# ionode.net
KiCad netlist of a schematic drawn in EAGLE
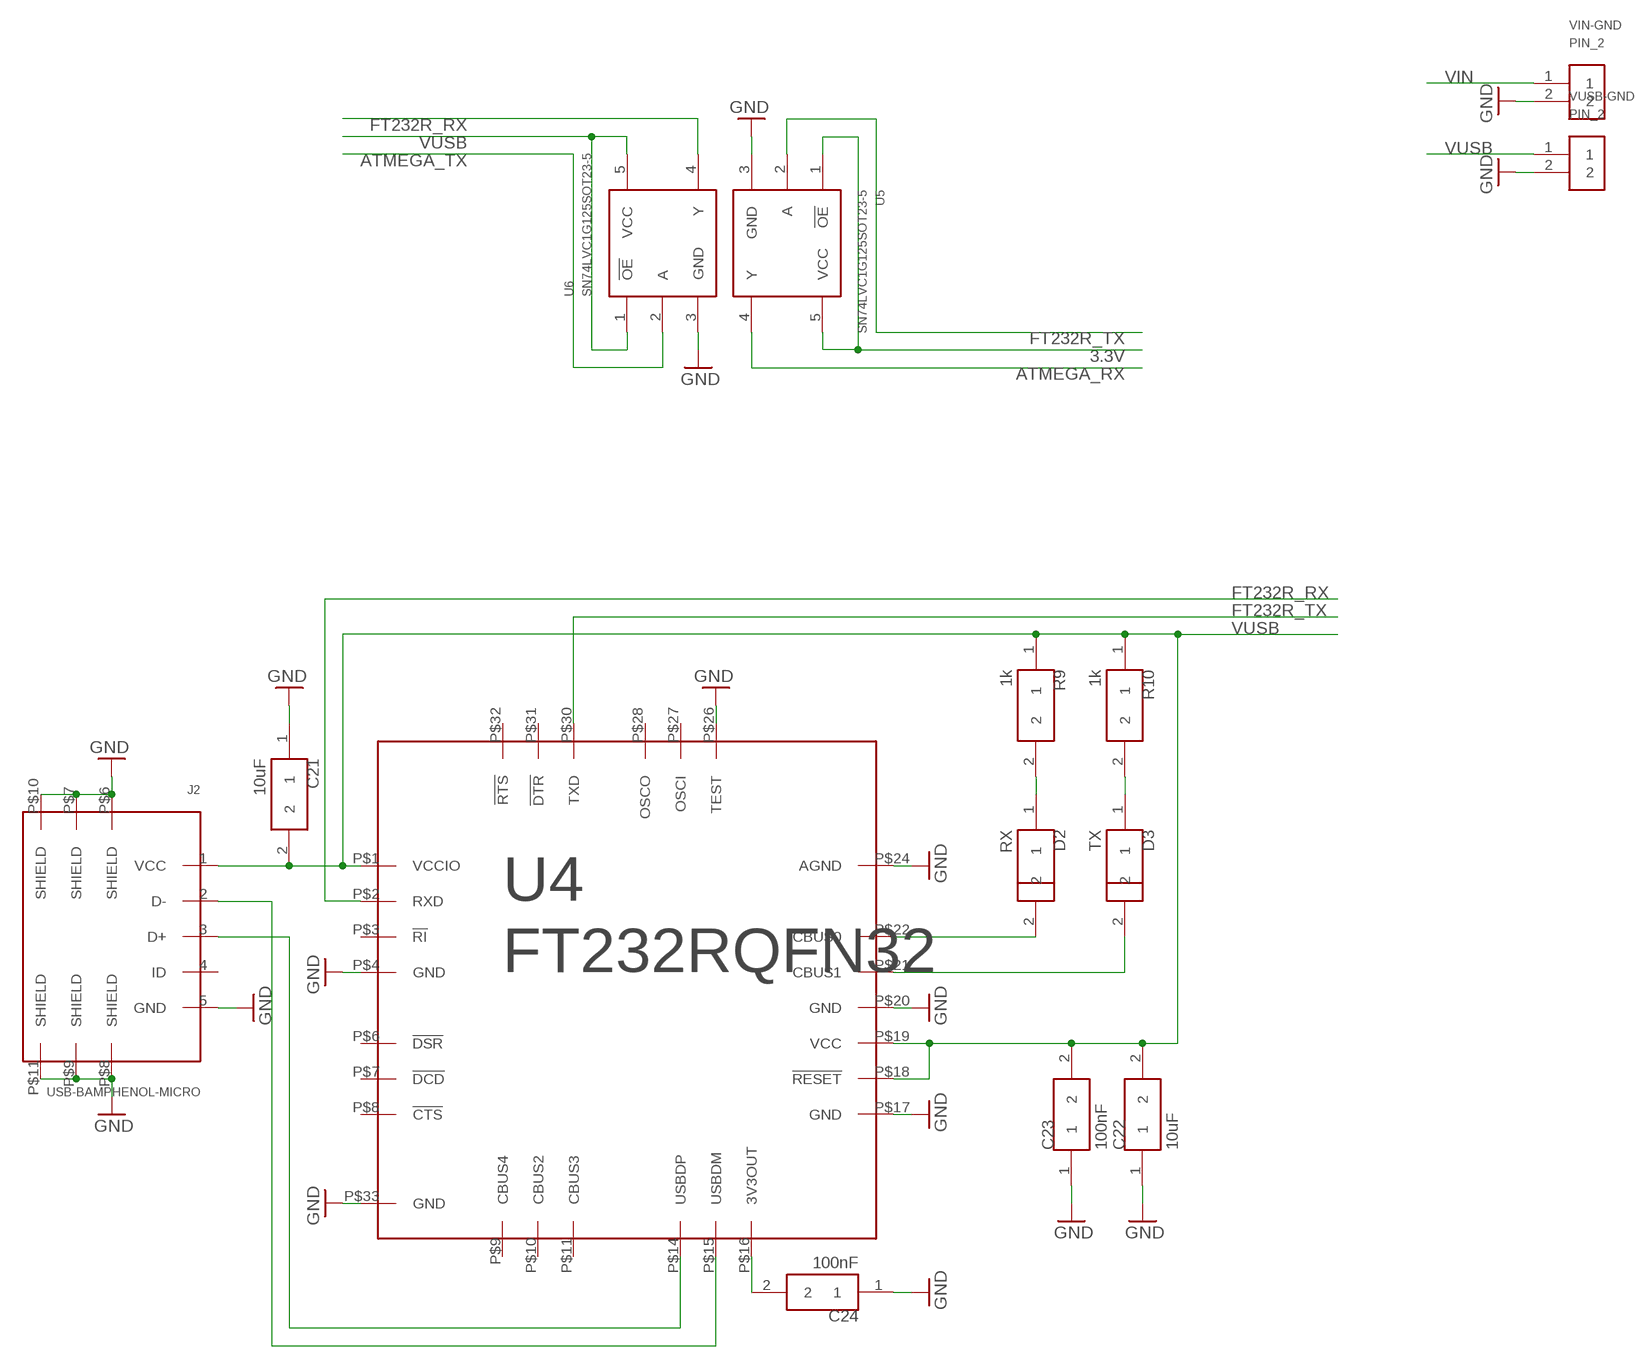
[diagram p0: schematic, sheet 1, part 1 of 2]
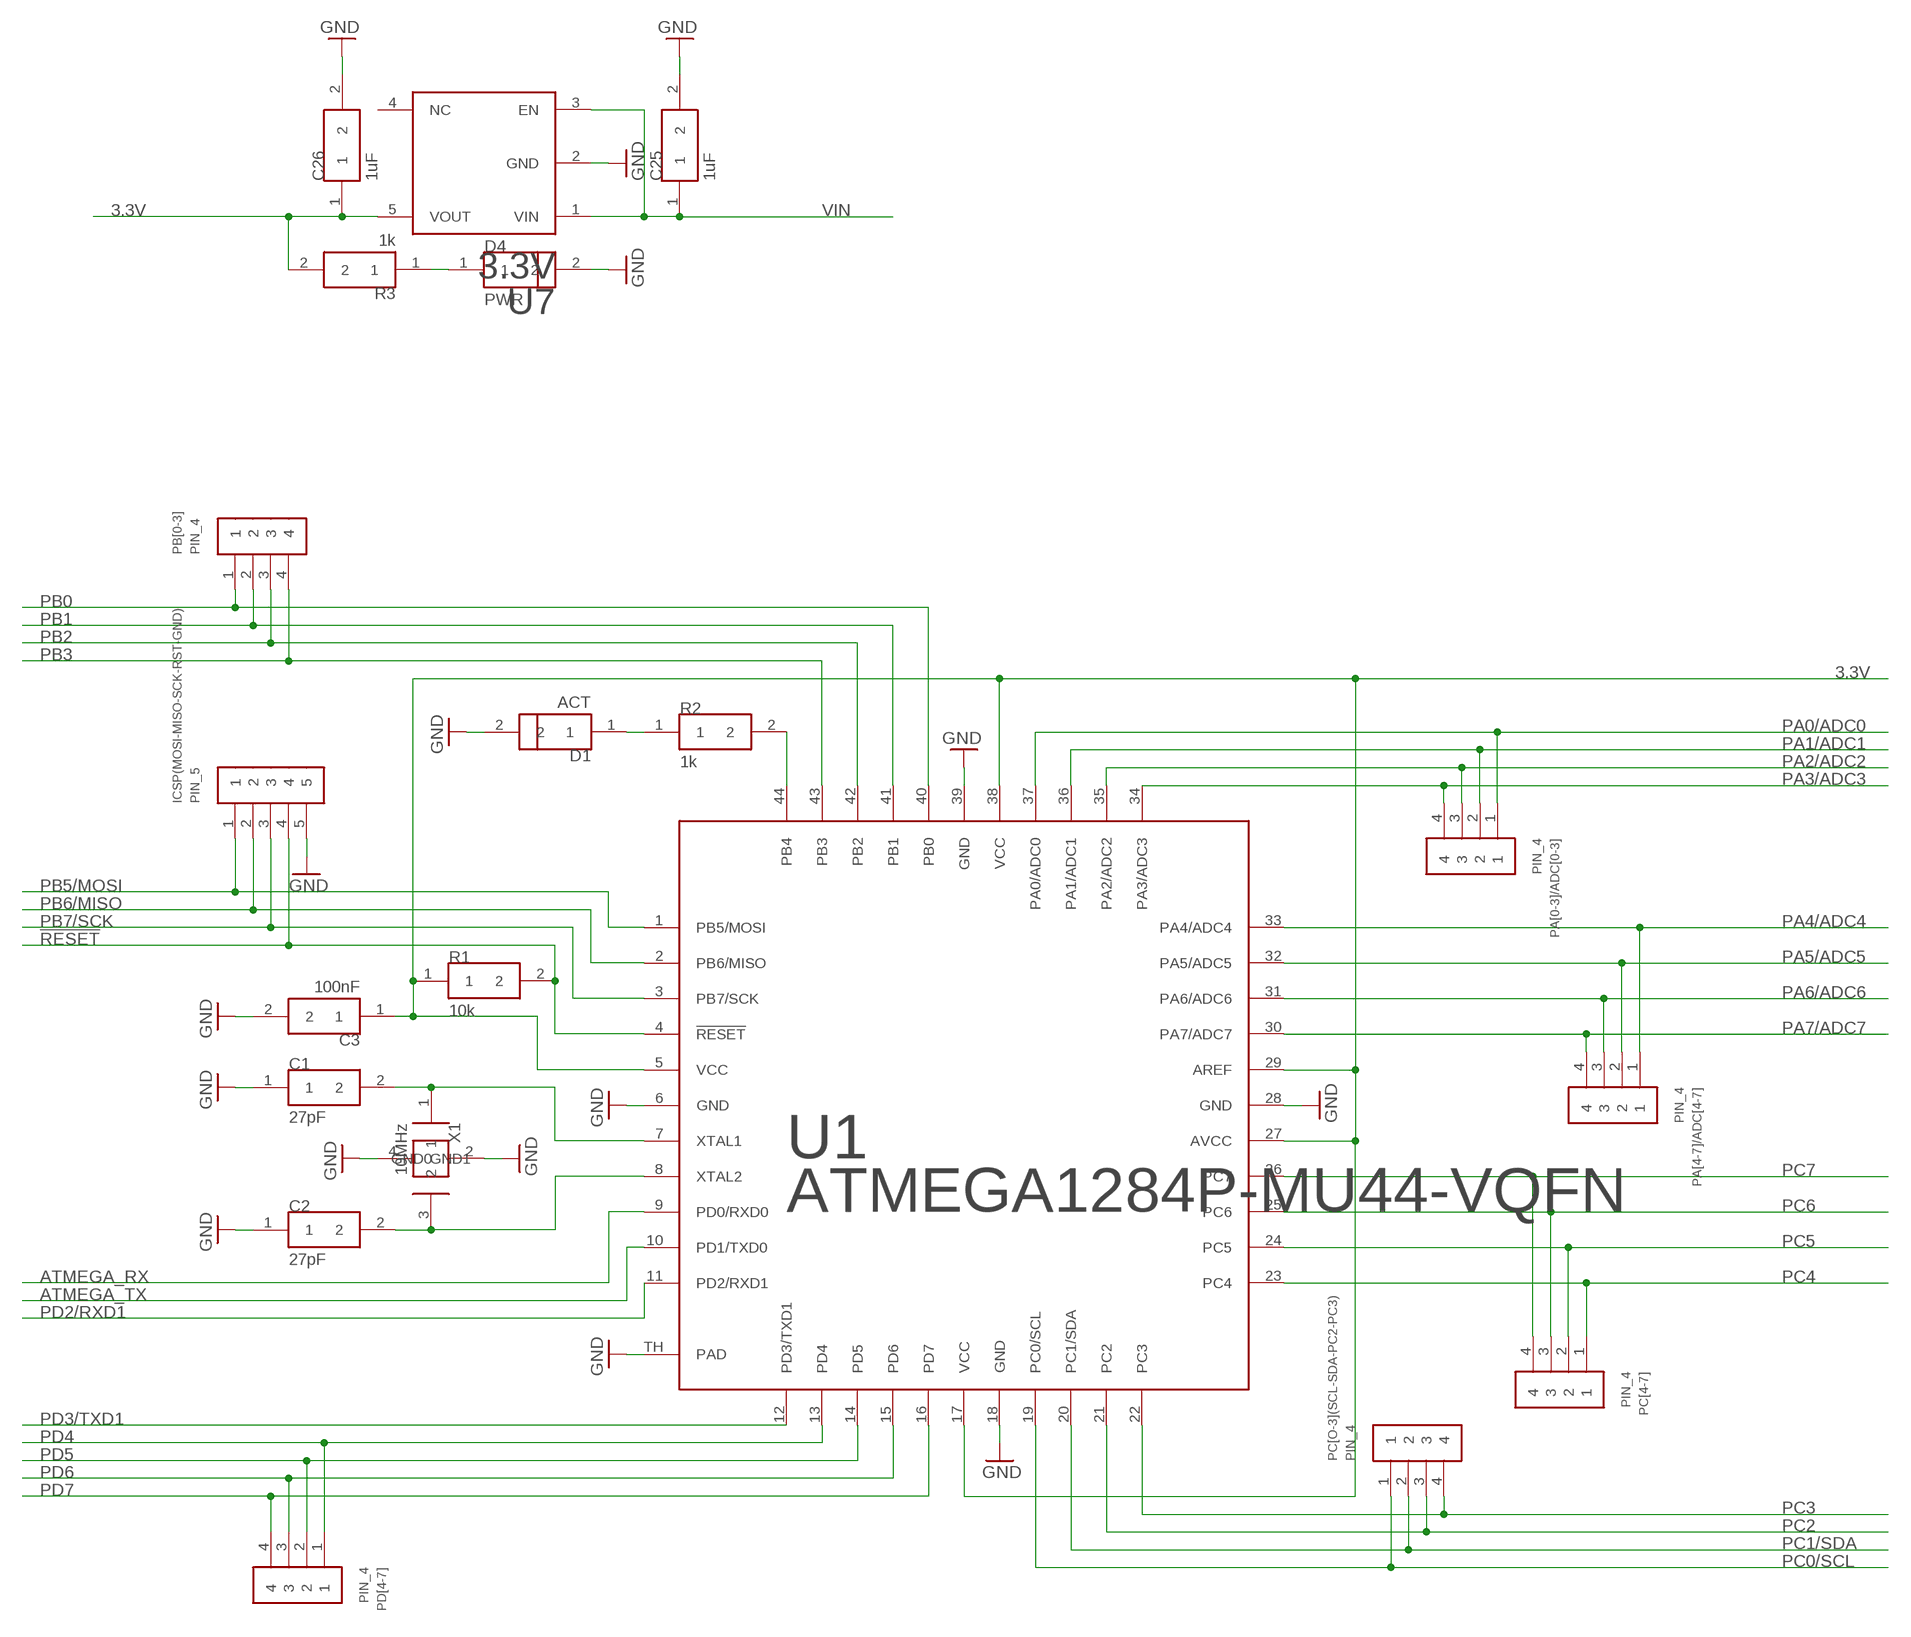
[diagram p1: schematic, sheet 1, part 2 of 2]

(export (version "E")
  (design (tool "Eeschema 10.0.6"))
  (components
    (comp (ref "C1")
      (value "27pF")
      (footprint "eagle-import:0805")
      (libsource (lib "eagle-import") (part "CAP0805"))
    )
    (comp (ref "C2")
      (value "27pF")
      (footprint "eagle-import:0805")
      (libsource (lib "eagle-import") (part "CAP0805"))
    )
    (comp (ref "C3")
      (value "100nF")
      (footprint "eagle-import:0805")
      (libsource (lib "eagle-import") (part "CAP0805"))
    )
    (comp (ref "C21")
      (value "10uF")
      (footprint "eagle-import:0805")
      (libsource (lib "eagle-import") (part "CAP0805"))
    )
    (comp (ref "C22")
      (value "10uF")
      (footprint "eagle-import:0805")
      (libsource (lib "eagle-import") (part "CAP0805"))
    )
    (comp (ref "C23")
      (value "100nF")
      (footprint "eagle-import:0805")
      (libsource (lib "eagle-import") (part "CAP0805"))
    )
    (comp (ref "C24")
      (value "100nF")
      (footprint "eagle-import:0805")
      (libsource (lib "eagle-import") (part "CAP0805"))
    )
    (comp (ref "C25")
      (value "1uF")
      (footprint "eagle-import:0805")
      (libsource (lib "eagle-import") (part "CAP0805"))
    )
    (comp (ref "C26")
      (value "1uF")
      (footprint "eagle-import:0805")
      (libsource (lib "eagle-import") (part "CAP0805"))
    )
    (comp (ref "D1")
      (value "ACT")
      (footprint "eagle-import:0805")
      (libsource (lib "eagle-import") (part "LED0805"))
    )
    (comp (ref "D2")
      (value "RX")
      (footprint "eagle-import:0805")
      (libsource (lib "eagle-import") (part "LED0805"))
    )
    (comp (ref "D3")
      (value "TX")
      (footprint "eagle-import:0805")
      (libsource (lib "eagle-import") (part "LED0805"))
    )
    (comp (ref "D4")
      (value "PWR")
      (footprint "eagle-import:0805")
      (libsource (lib "eagle-import") (part "LED0805"))
    )
    (comp (ref "ICSP(MOSI-MISO-SCK-RST-GND)")
      (value "PIN_5")
      (footprint "eagle-import:PIN_5")
      (libsource (lib "eagle-import") (part "PIN_5"))
    )
    (comp (ref "J2")
      (value "USB-BAMPHENOL-MICRO")
      (footprint "eagle-import:AMPHENOL-USB-MICRO-B")
      (libsource (lib "eagle-import") (part "USB-BAMPHENOL-MICRO"))
    )
    (comp (ref "PA[0-3]/ADC[0-3]")
      (value "PIN_4")
      (footprint "eagle-import:PIN_4")
      (libsource (lib "eagle-import") (part "PIN_4"))
    )
    (comp (ref "PA[4-7]/ADC[4-7]")
      (value "PIN_4")
      (footprint "eagle-import:PIN_4")
      (libsource (lib "eagle-import") (part "PIN_4"))
    )
    (comp (ref "PB[0-3]")
      (value "PIN_4")
      (footprint "eagle-import:PIN_4")
      (libsource (lib "eagle-import") (part "PIN_4"))
    )
    (comp (ref "PC[4-7]")
      (value "PIN_4")
      (footprint "eagle-import:PIN_4")
      (libsource (lib "eagle-import") (part "PIN_4"))
    )
    (comp (ref "PC[O-3](SCL-SDA-PC2-PC3)")
      (value "PIN_4")
      (footprint "eagle-import:PIN_4")
      (libsource (lib "eagle-import") (part "PIN_4"))
    )
    (comp (ref "PD[4-7]")
      (value "PIN_4")
      (footprint "eagle-import:PIN_4")
      (libsource (lib "eagle-import") (part "PIN_4"))
    )
    (comp (ref "R1")
      (value "10k")
      (footprint "eagle-import:0805")
      (libsource (lib "eagle-import") (part "RES0805"))
    )
    (comp (ref "R2")
      (value "1k")
      (footprint "eagle-import:0805")
      (libsource (lib "eagle-import") (part "RES0805"))
    )
    (comp (ref "R3")
      (value "1k")
      (footprint "eagle-import:0805")
      (libsource (lib "eagle-import") (part "RES0805"))
    )
    (comp (ref "R9")
      (value "1k")
      (footprint "eagle-import:0805")
      (libsource (lib "eagle-import") (part "RES0805"))
    )
    (comp (ref "R10")
      (value "1k")
      (footprint "eagle-import:0805")
      (libsource (lib "eagle-import") (part "RES0805"))
    )
    (comp (ref "U1")
      (value "ATMEGA1284P-MU44-VQFN")
      (footprint "eagle-import:44-VQFN")
      (libsource (lib "eagle-import") (part "ATMEGA1284P-MU44-VQFN"))
    )
    (comp (ref "U4")
      (value "FT232RQFN32")
      (footprint "eagle-import:32-VQFN")
      (libsource (lib "eagle-import") (part "FT232RQFN32"))
    )
    (comp (ref "U5")
      (value "SN74LVC1G125SOT23-5")
      (footprint "eagle-import:SOT23-5")
      (libsource (lib "eagle-import") (part "SN74LVC1G125SOT23-5"))
    )
    (comp (ref "U6")
      (value "SN74LVC1G125SOT23-5")
      (footprint "eagle-import:SOT23-5")
      (libsource (lib "eagle-import") (part "SN74LVC1G125SOT23-5"))
    )
    (comp (ref "U7")
      (value "3.3V")
      (footprint "eagle-import:SOT23-5")
      (libsource (lib "eagle-import") (part "LP3985SOT23-5"))
    )
    (comp (ref "VIN-GND")
      (value "PIN_2")
      (footprint "eagle-import:PIN_2")
      (libsource (lib "eagle-import") (part "PIN_2"))
    )
    (comp (ref "VUSB-GND")
      (value "PIN_2")
      (footprint "eagle-import:PIN_2")
      (libsource (lib "eagle-import") (part "PIN_2"))
    )
    (comp (ref "X1")
      (value "10MHz")
      (footprint "eagle-import:XTAL_3225")
      (libsource (lib "eagle-import") (part "XTAL_GNDSMD_3225"))
    )
  )
  (nets
    (net (code "1") (name "/3.3V") (class "Default")
      (node (ref "C26") (pin "1") (pinfunction "1_1") (pintype "bidirectional"))
      (node (ref "C3") (pin "1") (pinfunction "1_1") (pintype "bidirectional"))
      (node (ref "R1") (pin "1") (pinfunction "1_1") (pintype "bidirectional"))
      (node (ref "R3") (pin "2") (pinfunction "2_2") (pintype "bidirectional"))
      (node (ref "U1") (pin "17") (pinfunction "VCC_17") (pintype "bidirectional"))
      (node (ref "U1") (pin "27") (pinfunction "AVCC_27") (pintype "bidirectional"))
      (node (ref "U1") (pin "29") (pinfunction "AREF_29") (pintype "bidirectional"))
      (node (ref "U1") (pin "38") (pinfunction "VCC_38") (pintype "bidirectional"))
      (node (ref "U1") (pin "5") (pinfunction "VCC_5") (pintype "bidirectional"))
      (node (ref "U5") (pin "1") (pinfunction "~{OE}_1") (pintype "bidirectional"))
      (node (ref "U5") (pin "5") (pinfunction "VCC_5") (pintype "bidirectional"))
      (node (ref "U7") (pin "5") (pinfunction "VOUT_5") (pintype "bidirectional"))
    )
    (net (code "2") (name "/ATMEGA_RX") (class "Default")
      (node (ref "U1") (pin "9") (pinfunction "PD0/RXD0_9") (pintype "bidirectional"))
      (node (ref "U5") (pin "4") (pinfunction "Y_4") (pintype "bidirectional"))
    )
    (net (code "3") (name "/ATMEGA_TX") (class "Default")
      (node (ref "U1") (pin "10") (pinfunction "PD1/TXD0_10") (pintype "bidirectional"))
      (node (ref "U6") (pin "2") (pinfunction "A_2") (pintype "bidirectional"))
    )
    (net (code "4") (name "/FT232R_RX") (class "Default")
      (node (ref "U4") (pin "P$2") (pinfunction "RXD_P$2") (pintype "bidirectional"))
      (node (ref "U6") (pin "4") (pinfunction "Y_4") (pintype "bidirectional"))
    )
    (net (code "5") (name "/FT232R_TX") (class "Default")
      (node (ref "U4") (pin "P$30") (pinfunction "TXD_P$30") (pintype "bidirectional"))
      (node (ref "U5") (pin "2") (pinfunction "A_2") (pintype "bidirectional"))
    )
    (net (code "6") (name "/PA0{slash}ADC0") (class "Default")
      (node (ref "PA[0-3]/ADC[0-3]") (pin "1") (pinfunction "1_1") (pintype "bidirectional"))
      (node (ref "U1") (pin "37") (pinfunction "PA0/ADC0_37") (pintype "bidirectional"))
    )
    (net (code "7") (name "/PA1{slash}ADC1") (class "Default")
      (node (ref "PA[0-3]/ADC[0-3]") (pin "2") (pinfunction "2_2") (pintype "bidirectional"))
      (node (ref "U1") (pin "36") (pinfunction "PA1/ADC1_36") (pintype "bidirectional"))
    )
    (net (code "8") (name "/PA2{slash}ADC2") (class "Default")
      (node (ref "PA[0-3]/ADC[0-3]") (pin "3") (pinfunction "3_3") (pintype "bidirectional"))
      (node (ref "U1") (pin "35") (pinfunction "PA2/ADC2_35") (pintype "bidirectional"))
    )
    (net (code "9") (name "/PA3{slash}ADC3") (class "Default")
      (node (ref "PA[0-3]/ADC[0-3]") (pin "4") (pinfunction "4_4") (pintype "bidirectional"))
      (node (ref "U1") (pin "34") (pinfunction "PA3/ADC3_34") (pintype "bidirectional"))
    )
    (net (code "10") (name "/PA4{slash}ADC4") (class "Default")
      (node (ref "PA[4-7]/ADC[4-7]") (pin "1") (pinfunction "1_1") (pintype "bidirectional"))
      (node (ref "U1") (pin "33") (pinfunction "PA4/ADC4_33") (pintype "bidirectional"))
    )
    (net (code "11") (name "/PA5{slash}ADC5") (class "Default")
      (node (ref "PA[4-7]/ADC[4-7]") (pin "2") (pinfunction "2_2") (pintype "bidirectional"))
      (node (ref "U1") (pin "32") (pinfunction "PA5/ADC5_32") (pintype "bidirectional"))
    )
    (net (code "12") (name "/PA6{slash}ADC6") (class "Default")
      (node (ref "PA[4-7]/ADC[4-7]") (pin "3") (pinfunction "3_3") (pintype "bidirectional"))
      (node (ref "U1") (pin "31") (pinfunction "PA6/ADC6_31") (pintype "bidirectional"))
    )
    (net (code "13") (name "/PA7{slash}ADC7") (class "Default")
      (node (ref "PA[4-7]/ADC[4-7]") (pin "4") (pinfunction "4_4") (pintype "bidirectional"))
      (node (ref "U1") (pin "30") (pinfunction "PA7/ADC7_30") (pintype "bidirectional"))
    )
    (net (code "14") (name "/PB0") (class "Default")
      (node (ref "PB[0-3]") (pin "1") (pinfunction "1_1") (pintype "bidirectional"))
      (node (ref "U1") (pin "40") (pinfunction "PB0_40") (pintype "bidirectional"))
    )
    (net (code "15") (name "/PB1") (class "Default")
      (node (ref "PB[0-3]") (pin "2") (pinfunction "2_2") (pintype "bidirectional"))
      (node (ref "U1") (pin "41") (pinfunction "PB1_41") (pintype "bidirectional"))
    )
    (net (code "16") (name "/PB2") (class "Default")
      (node (ref "PB[0-3]") (pin "3") (pinfunction "3_3") (pintype "bidirectional"))
      (node (ref "U1") (pin "42") (pinfunction "PB2_42") (pintype "bidirectional"))
    )
    (net (code "17") (name "/PB3") (class "Default")
      (node (ref "PB[0-3]") (pin "4") (pinfunction "4_4") (pintype "bidirectional"))
      (node (ref "U1") (pin "43") (pinfunction "PB3_43") (pintype "bidirectional"))
    )
    (net (code "18") (name "/PB5{slash}MOSI") (class "Default")
      (node (ref "ICSP(MOSI-MISO-SCK-RST-GND)") (pin "1") (pinfunction "1_1") (pintype "bidirectional"))
      (node (ref "U1") (pin "1") (pinfunction "PB5/MOSI_1") (pintype "bidirectional"))
    )
    (net (code "19") (name "/PB6{slash}MISO") (class "Default")
      (node (ref "ICSP(MOSI-MISO-SCK-RST-GND)") (pin "2") (pinfunction "2_2") (pintype "bidirectional"))
      (node (ref "U1") (pin "2") (pinfunction "PB6/MISO_2") (pintype "bidirectional"))
    )
    (net (code "20") (name "/PB7{slash}SCK") (class "Default")
      (node (ref "ICSP(MOSI-MISO-SCK-RST-GND)") (pin "3") (pinfunction "3_3") (pintype "bidirectional"))
      (node (ref "U1") (pin "3") (pinfunction "PB7/SCK_3") (pintype "bidirectional"))
    )
    (net (code "21") (name "/PC0{slash}SCL") (class "Default")
      (node (ref "PC[O-3](SCL-SDA-PC2-PC3)") (pin "1") (pinfunction "1_1") (pintype "bidirectional"))
      (node (ref "U1") (pin "19") (pinfunction "PC0/SCL_19") (pintype "bidirectional"))
    )
    (net (code "22") (name "/PC1{slash}SDA") (class "Default")
      (node (ref "PC[O-3](SCL-SDA-PC2-PC3)") (pin "2") (pinfunction "2_2") (pintype "bidirectional"))
      (node (ref "U1") (pin "20") (pinfunction "PC1/SDA_20") (pintype "bidirectional"))
    )
    (net (code "23") (name "/PC2") (class "Default")
      (node (ref "PC[O-3](SCL-SDA-PC2-PC3)") (pin "3") (pinfunction "3_3") (pintype "bidirectional"))
      (node (ref "U1") (pin "21") (pinfunction "PC2_21") (pintype "bidirectional"))
    )
    (net (code "24") (name "/PC3") (class "Default")
      (node (ref "PC[O-3](SCL-SDA-PC2-PC3)") (pin "4") (pinfunction "4_4") (pintype "bidirectional"))
      (node (ref "U1") (pin "22") (pinfunction "PC3_22") (pintype "bidirectional"))
    )
    (net (code "25") (name "/PC4") (class "Default")
      (node (ref "PC[4-7]") (pin "1") (pinfunction "1_1") (pintype "bidirectional"))
      (node (ref "U1") (pin "23") (pinfunction "PC4_23") (pintype "bidirectional"))
    )
    (net (code "26") (name "/PC5") (class "Default")
      (node (ref "PC[4-7]") (pin "2") (pinfunction "2_2") (pintype "bidirectional"))
      (node (ref "U1") (pin "24") (pinfunction "PC5_24") (pintype "bidirectional"))
    )
    (net (code "27") (name "/PC6") (class "Default")
      (node (ref "PC[4-7]") (pin "3") (pinfunction "3_3") (pintype "bidirectional"))
      (node (ref "U1") (pin "25") (pinfunction "PC6_25") (pintype "bidirectional"))
    )
    (net (code "28") (name "/PC7") (class "Default")
      (node (ref "PC[4-7]") (pin "4") (pinfunction "4_4") (pintype "bidirectional"))
      (node (ref "U1") (pin "26") (pinfunction "PC7_26") (pintype "bidirectional"))
    )
    (net (code "29") (name "/PD2{slash}RXD1") (class "Default")
      (node (ref "U1") (pin "11") (pinfunction "PD2/RXD1_11") (pintype "bidirectional"))
    )
    (net (code "30") (name "/PD3{slash}TXD1") (class "Default")
      (node (ref "U1") (pin "12") (pinfunction "PD3/TXD1_12") (pintype "bidirectional"))
    )
    (net (code "31") (name "/PD4") (class "Default")
      (node (ref "PD[4-7]") (pin "1") (pinfunction "1_1") (pintype "bidirectional"))
      (node (ref "U1") (pin "13") (pinfunction "PD4_13") (pintype "bidirectional"))
    )
    (net (code "32") (name "/PD5") (class "Default")
      (node (ref "PD[4-7]") (pin "2") (pinfunction "2_2") (pintype "bidirectional"))
      (node (ref "U1") (pin "14") (pinfunction "PD5_14") (pintype "bidirectional"))
    )
    (net (code "33") (name "/PD6") (class "Default")
      (node (ref "PD[4-7]") (pin "3") (pinfunction "3_3") (pintype "bidirectional"))
      (node (ref "U1") (pin "15") (pinfunction "PD6_15") (pintype "bidirectional"))
    )
    (net (code "34") (name "/PD7") (class "Default")
      (node (ref "PD[4-7]") (pin "4") (pinfunction "4_4") (pintype "bidirectional"))
      (node (ref "U1") (pin "16") (pinfunction "PD7_16") (pintype "bidirectional"))
    )
    (net (code "35") (name "/VIN") (class "Default")
      (node (ref "C25") (pin "1") (pinfunction "1_1") (pintype "bidirectional"))
      (node (ref "U7") (pin "1") (pinfunction "VIN_1") (pintype "bidirectional"))
      (node (ref "U7") (pin "3") (pinfunction "EN_3") (pintype "bidirectional"))
      (node (ref "VIN-GND") (pin "1") (pinfunction "1_1") (pintype "bidirectional"))
    )
    (net (code "36") (name "/VUSB") (class "Default")
      (node (ref "C21") (pin "2") (pinfunction "2_2") (pintype "bidirectional"))
      (node (ref "C22") (pin "2") (pinfunction "2_2") (pintype "bidirectional"))
      (node (ref "C23") (pin "2") (pinfunction "2_2") (pintype "bidirectional"))
      (node (ref "J2") (pin "1") (pinfunction "VCC_1") (pintype "bidirectional"))
      (node (ref "R10") (pin "1") (pinfunction "1_1") (pintype "bidirectional"))
      (node (ref "R9") (pin "1") (pinfunction "1_1") (pintype "bidirectional"))
      (node (ref "U4") (pin "P$1") (pinfunction "VCCIO_P$1") (pintype "bidirectional"))
      (node (ref "U4") (pin "P$18") (pinfunction "~{RESET}_P$18") (pintype "bidirectional"))
      (node (ref "U4") (pin "P$19") (pinfunction "VCC_P$19") (pintype "bidirectional"))
      (node (ref "U6") (pin "1") (pinfunction "~{OE}_1") (pintype "bidirectional"))
      (node (ref "U6") (pin "5") (pinfunction "VCC_5") (pintype "bidirectional"))
      (node (ref "VUSB-GND") (pin "1") (pinfunction "1_1") (pintype "bidirectional"))
    )
    (net (code "37") (name "/~{RESET}") (class "Default")
      (node (ref "ICSP(MOSI-MISO-SCK-RST-GND)") (pin "4") (pinfunction "4_4") (pintype "bidirectional"))
      (node (ref "R1") (pin "2") (pinfunction "2_2") (pintype "bidirectional"))
      (node (ref "U1") (pin "4") (pinfunction "~{RESET}_4") (pintype "bidirectional"))
    )
    (net (code "38") (name "GND") (class "Default")
      (node (ref "C1") (pin "1") (pinfunction "1_1") (pintype "bidirectional"))
      (node (ref "C2") (pin "1") (pinfunction "1_1") (pintype "bidirectional"))
      (node (ref "C21") (pin "1") (pinfunction "1_1") (pintype "bidirectional"))
      (node (ref "C22") (pin "1") (pinfunction "1_1") (pintype "bidirectional"))
      (node (ref "C23") (pin "1") (pinfunction "1_1") (pintype "bidirectional"))
      (node (ref "C24") (pin "1") (pinfunction "1_1") (pintype "bidirectional"))
      (node (ref "C25") (pin "2") (pinfunction "2_2") (pintype "bidirectional"))
      (node (ref "C26") (pin "2") (pinfunction "2_2") (pintype "bidirectional"))
      (node (ref "C3") (pin "2") (pinfunction "2_2") (pintype "bidirectional"))
      (node (ref "D1") (pin "2") (pinfunction "2_2") (pintype "bidirectional"))
      (node (ref "D4") (pin "2") (pinfunction "2_2") (pintype "bidirectional"))
      (node (ref "ICSP(MOSI-MISO-SCK-RST-GND)") (pin "5") (pinfunction "5_5") (pintype "bidirectional"))
      (node (ref "J2") (pin "5") (pinfunction "GND_5") (pintype "bidirectional"))
      (node (ref "J2") (pin "P$10") (pinfunction "SHIELD_P$10") (pintype "bidirectional"))
      (node (ref "J2") (pin "P$11") (pinfunction "SHIELD_P$11") (pintype "bidirectional"))
      (node (ref "J2") (pin "P$6") (pinfunction "SHIELD_P$6") (pintype "bidirectional"))
      (node (ref "J2") (pin "P$7") (pinfunction "SHIELD_P$7") (pintype "bidirectional"))
      (node (ref "J2") (pin "P$8") (pinfunction "SHIELD_P$8") (pintype "bidirectional"))
      (node (ref "J2") (pin "P$9") (pinfunction "SHIELD_P$9") (pintype "bidirectional"))
      (node (ref "U1") (pin "18") (pinfunction "GND_18") (pintype "bidirectional"))
      (node (ref "U1") (pin "28") (pinfunction "GND_28") (pintype "bidirectional"))
      (node (ref "U1") (pin "39") (pinfunction "GND_39") (pintype "bidirectional"))
      (node (ref "U1") (pin "6") (pinfunction "GND_6") (pintype "bidirectional"))
      (node (ref "U1") (pin "TH") (pinfunction "PAD_TH") (pintype "bidirectional"))
      (node (ref "U4") (pin "P$17") (pinfunction "GND_P$17") (pintype "bidirectional"))
      (node (ref "U4") (pin "P$20") (pinfunction "GND_P$20") (pintype "bidirectional"))
      (node (ref "U4") (pin "P$24") (pinfunction "AGND_P$24") (pintype "bidirectional"))
      (node (ref "U4") (pin "P$26") (pinfunction "TEST_P$26") (pintype "bidirectional"))
      (node (ref "U4") (pin "P$33") (pinfunction "GND_P$33") (pintype "bidirectional"))
      (node (ref "U4") (pin "P$4") (pinfunction "GND_P$4") (pintype "bidirectional"))
      (node (ref "U5") (pin "3") (pinfunction "GND_3") (pintype "bidirectional"))
      (node (ref "U6") (pin "3") (pinfunction "GND_3") (pintype "bidirectional"))
      (node (ref "U7") (pin "2") (pinfunction "GND_2") (pintype "bidirectional"))
      (node (ref "VIN-GND") (pin "2") (pinfunction "2_2") (pintype "bidirectional"))
      (node (ref "VUSB-GND") (pin "2") (pinfunction "2_2") (pintype "bidirectional"))
      (node (ref "X1") (pin "2") (pinfunction "GND0_2") (pintype "bidirectional"))
      (node (ref "X1") (pin "4") (pinfunction "GND1_4") (pintype "bidirectional"))
    )
    (net (code "39") (name "Net-(D1-Pad1)") (class "Default")
      (node (ref "D1") (pin "1") (pinfunction "1_1") (pintype "bidirectional"))
      (node (ref "R2") (pin "1") (pinfunction "1_1") (pintype "bidirectional"))
    )
    (net (code "40") (name "Net-(D2-Pad1)") (class "Default")
      (node (ref "D2") (pin "1") (pinfunction "1_1") (pintype "bidirectional"))
      (node (ref "R9") (pin "2") (pinfunction "2_2") (pintype "bidirectional"))
    )
    (net (code "41") (name "Net-(D3-Pad1)") (class "Default")
      (node (ref "D3") (pin "1") (pinfunction "1_1") (pintype "bidirectional"))
      (node (ref "R10") (pin "2") (pinfunction "2_2") (pintype "bidirectional"))
    )
    (net (code "42") (name "Net-(D4-Pad1)") (class "Default")
      (node (ref "D4") (pin "1") (pinfunction "1_1") (pintype "bidirectional"))
      (node (ref "R3") (pin "1") (pinfunction "1_1") (pintype "bidirectional"))
    )
    (net (code "43") (name "Net-(J2-D+)") (class "Default")
      (node (ref "J2") (pin "3") (pinfunction "D+_3") (pintype "bidirectional"))
      (node (ref "U4") (pin "P$14") (pinfunction "USBDP_P$14") (pintype "bidirectional"))
    )
    (net (code "44") (name "Net-(J2-D-)") (class "Default")
      (node (ref "J2") (pin "2") (pinfunction "D-_2") (pintype "bidirectional"))
      (node (ref "U4") (pin "P$15") (pinfunction "USBDM_P$15") (pintype "bidirectional"))
    )
    (net (code "45") (name "Net-(U1-PB4)") (class "Default")
      (node (ref "R2") (pin "2") (pinfunction "2_2") (pintype "bidirectional"))
      (node (ref "U1") (pin "44") (pinfunction "PB4_44") (pintype "bidirectional"))
    )
    (net (code "46") (name "Net-(U1-XTAL1)") (class "Default")
      (node (ref "C1") (pin "2") (pinfunction "2_2") (pintype "bidirectional"))
      (node (ref "U1") (pin "7") (pinfunction "XTAL1_7") (pintype "bidirectional"))
      (node (ref "X1") (pin "1") (pinfunction "1_1") (pintype "bidirectional"))
    )
    (net (code "47") (name "Net-(U1-XTAL2)") (class "Default")
      (node (ref "C2") (pin "2") (pinfunction "2_2") (pintype "bidirectional"))
      (node (ref "U1") (pin "8") (pinfunction "XTAL2_8") (pintype "bidirectional"))
      (node (ref "X1") (pin "3") (pinfunction "2_3") (pintype "bidirectional"))
    )
    (net (code "48") (name "Net-(U4-3V3OUT)") (class "Default")
      (node (ref "C24") (pin "2") (pinfunction "2_2") (pintype "bidirectional"))
      (node (ref "U4") (pin "P$16") (pinfunction "3V3OUT_P$16") (pintype "bidirectional"))
    )
    (net (code "49") (name "Net-(U4-CBUS0)") (class "Default")
      (node (ref "D2") (pin "2") (pinfunction "2_2") (pintype "bidirectional"))
      (node (ref "U4") (pin "P$22") (pinfunction "CBUS0_P$22") (pintype "bidirectional"))
    )
    (net (code "50") (name "Net-(U4-CBUS1)") (class "Default")
      (node (ref "D3") (pin "2") (pinfunction "2_2") (pintype "bidirectional"))
      (node (ref "U4") (pin "P$21") (pinfunction "CBUS1_P$21") (pintype "bidirectional"))
    )
    (net (code "51") (name "unconnected-(J2-ID-Pad4)") (class "Default")
      (node (ref "J2") (pin "4") (pinfunction "ID_4") (pintype "bidirectional"))
    )
    (net (code "52") (name "unconnected-(U4-CBUS2-PadP$10)") (class "Default")
      (node (ref "U4") (pin "P$10") (pinfunction "CBUS2_P$10") (pintype "bidirectional"))
    )
    (net (code "53") (name "unconnected-(U4-CBUS3-PadP$11)") (class "Default")
      (node (ref "U4") (pin "P$11") (pinfunction "CBUS3_P$11") (pintype "bidirectional"))
    )
    (net (code "54") (name "unconnected-(U4-CBUS4-PadP$9)") (class "Default")
      (node (ref "U4") (pin "P$9") (pinfunction "CBUS4_P$9") (pintype "bidirectional"))
    )
    (net (code "55") (name "unconnected-(U4-OSCI-PadP$27)") (class "Default")
      (node (ref "U4") (pin "P$27") (pinfunction "OSCI_P$27") (pintype "bidirectional"))
    )
    (net (code "56") (name "unconnected-(U4-OSCO-PadP$28)") (class "Default")
      (node (ref "U4") (pin "P$28") (pinfunction "OSCO_P$28") (pintype "bidirectional"))
    )
    (net (code "57") (name "unconnected-(U4-~{CTS}-PadP$8)") (class "Default")
      (node (ref "U4") (pin "P$8") (pinfunction "~{CTS}_P$8") (pintype "bidirectional"))
    )
    (net (code "58") (name "unconnected-(U4-~{DCD}-PadP$7)") (class "Default")
      (node (ref "U4") (pin "P$7") (pinfunction "~{DCD}_P$7") (pintype "bidirectional"))
    )
    (net (code "59") (name "unconnected-(U4-~{DSR}-PadP$6)") (class "Default")
      (node (ref "U4") (pin "P$6") (pinfunction "~{DSR}_P$6") (pintype "bidirectional"))
    )
    (net (code "60") (name "unconnected-(U4-~{DTR}-PadP$31)") (class "Default")
      (node (ref "U4") (pin "P$31") (pinfunction "~{DTR}_P$31") (pintype "bidirectional"))
    )
    (net (code "61") (name "unconnected-(U4-~{RI}-PadP$3)") (class "Default")
      (node (ref "U4") (pin "P$3") (pinfunction "~{RI}_P$3") (pintype "bidirectional"))
    )
    (net (code "62") (name "unconnected-(U4-~{RTS}-PadP$32)") (class "Default")
      (node (ref "U4") (pin "P$32") (pinfunction "~{RTS}_P$32") (pintype "bidirectional"))
    )
    (net (code "63") (name "unconnected-(U7-NC-Pad4)") (class "Default")
      (node (ref "U7") (pin "4") (pinfunction "NC_4") (pintype "bidirectional"))
    )
  )
)
